# Sensor_Acquisition_Board_Rev3.net
KiCad netlist of a schematic drawn in EAGLE
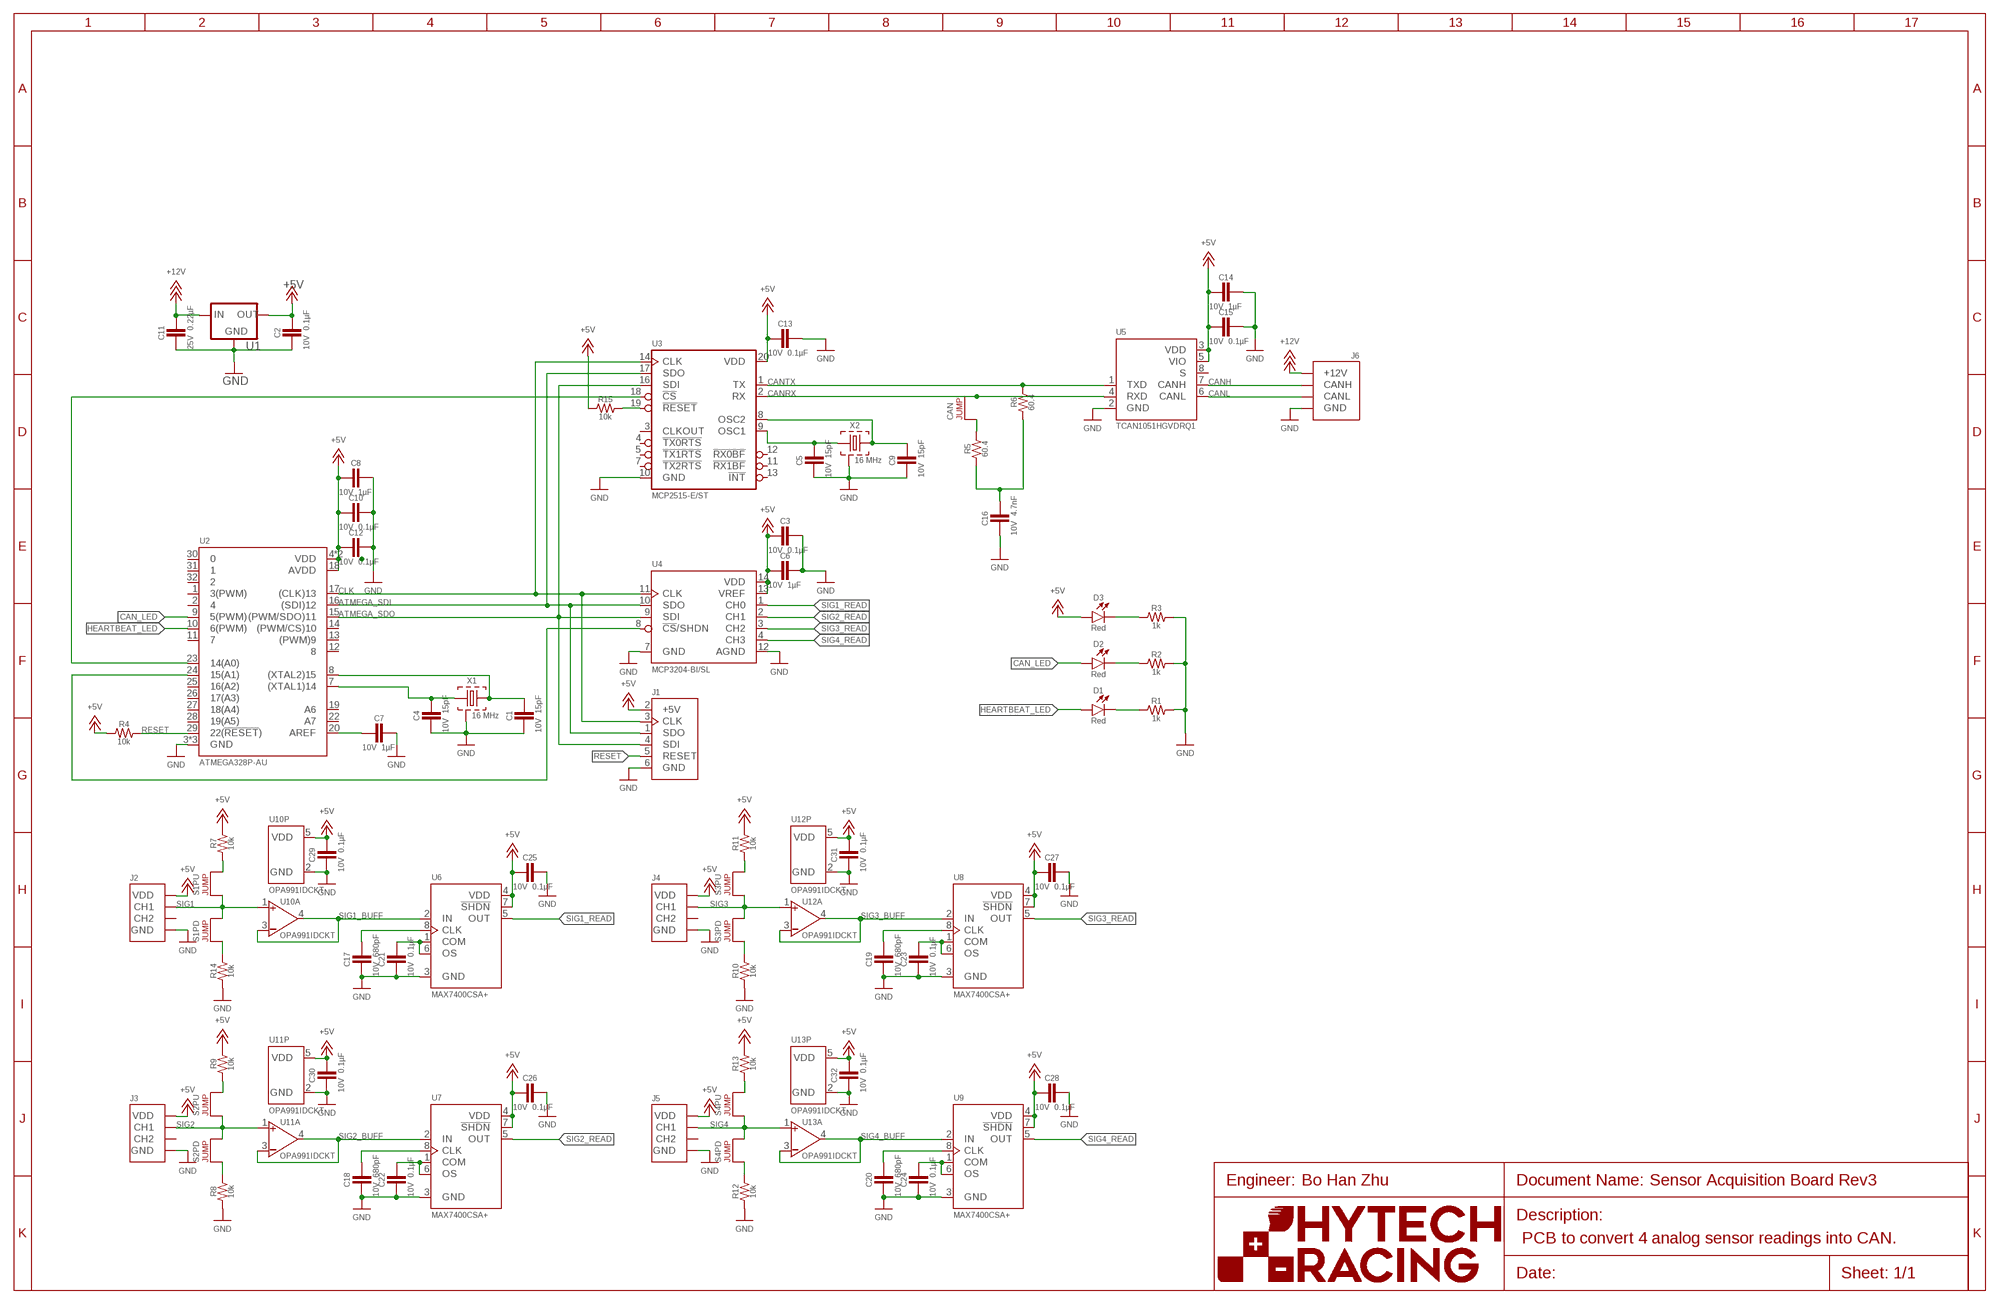
[diagram p0: schematic, sheet 1]

(export (version "E")
  (design (tool "Eeschema 10.0.6"))
  (components
    (comp (ref "C1")
      (value "CAPACITOR_0603_10V_15PF")
      (footprint "eagle-import:0603-CAP")
      (fields
        (field (name "CAPACITANCE") "15pF")
        (field (name "MANUFACTURER") "Vishay Vitramon")
        (field (name "MPN") "VJ0603A150FXQPW1BC")
        (field (name "TOLERANCE") "1%")
        (field (name "VOLTAGE") "10V")
      )
      (libsource (lib "eagle-import") (part "CAPACITOR_?_060310V_15PF"))
    )
    (comp (ref "C2")
      (value "CAPACITOR_0603_10V_0.1UF")
      (footprint "eagle-import:0603-CAP")
      (fields
        (field (name "CAPACITANCE") "0.1µF")
        (field (name "MANUFACTURER") "Vishay Vitramon")
        (field (name "MPN") "VJ0603Y104JXQPW1BC")
        (field (name "TOLERANCE") "5%")
        (field (name "VOLTAGE") "10V")
      )
      (libsource (lib "eagle-import") (part "CAPACITOR_?_060310V_0.1UF"))
    )
    (comp (ref "C3")
      (value "CAPACITOR_0603_10V_0.1UF")
      (footprint "eagle-import:0603-CAP")
      (fields
        (field (name "CAPACITANCE") "0.1µF")
        (field (name "MANUFACTURER") "Vishay Vitramon")
        (field (name "MPN") "VJ0603Y104JXQPW1BC")
        (field (name "TOLERANCE") "5%")
        (field (name "VOLTAGE") "10V")
      )
      (libsource (lib "eagle-import") (part "CAPACITOR_?_060310V_0.1UF"))
    )
    (comp (ref "C4")
      (value "CAPACITOR_0603_10V_15PF")
      (footprint "eagle-import:0603-CAP")
      (fields
        (field (name "CAPACITANCE") "15pF")
        (field (name "MANUFACTURER") "Vishay Vitramon")
        (field (name "MPN") "VJ0603A150FXQPW1BC")
        (field (name "TOLERANCE") "1%")
        (field (name "VOLTAGE") "10V")
      )
      (libsource (lib "eagle-import") (part "CAPACITOR_?_060310V_15PF"))
    )
    (comp (ref "C5")
      (value "CAPACITOR_0603_10V_15PF")
      (footprint "eagle-import:0603-CAP")
      (fields
        (field (name "CAPACITANCE") "15pF")
        (field (name "MANUFACTURER") "Vishay Vitramon")
        (field (name "MPN") "VJ0603A150FXQPW1BC")
        (field (name "TOLERANCE") "1%")
        (field (name "VOLTAGE") "10V")
      )
      (libsource (lib "eagle-import") (part "CAPACITOR_?_060310V_15PF"))
    )
    (comp (ref "C6")
      (value "CAPACITOR_0603_10V_1UF")
      (footprint "eagle-import:0603-CAP")
      (fields
        (field (name "CAPACITANCE") "1µF")
        (field (name "MANUFACTURER") "Yageo")
        (field (name "MPN") "CC0603KRX7R6BB105")
        (field (name "TOLERANCE") "10%")
        (field (name "VOLTAGE") "10V")
      )
      (libsource (lib "eagle-import") (part "CAPACITOR_?_060310V_1UF"))
    )
    (comp (ref "C7")
      (value "CAPACITOR_0603_10V_1UF")
      (footprint "eagle-import:0603-CAP")
      (fields
        (field (name "CAPACITANCE") "1µF")
        (field (name "MANUFACTURER") "Yageo")
        (field (name "MPN") "CC0603KRX7R6BB105")
        (field (name "TOLERANCE") "10%")
        (field (name "VOLTAGE") "10V")
      )
      (libsource (lib "eagle-import") (part "CAPACITOR_?_060310V_1UF"))
    )
    (comp (ref "C8")
      (value "CAPACITOR_0603_10V_1UF")
      (footprint "eagle-import:0603-CAP")
      (fields
        (field (name "CAPACITANCE") "1µF")
        (field (name "MANUFACTURER") "Yageo")
        (field (name "MPN") "CC0603KRX7R6BB105")
        (field (name "TOLERANCE") "10%")
        (field (name "VOLTAGE") "10V")
      )
      (libsource (lib "eagle-import") (part "CAPACITOR_?_060310V_1UF"))
    )
    (comp (ref "C9")
      (value "CAPACITOR_0603_10V_15PF")
      (footprint "eagle-import:0603-CAP")
      (fields
        (field (name "CAPACITANCE") "15pF")
        (field (name "MANUFACTURER") "Vishay Vitramon")
        (field (name "MPN") "VJ0603A150FXQPW1BC")
        (field (name "TOLERANCE") "1%")
        (field (name "VOLTAGE") "10V")
      )
      (libsource (lib "eagle-import") (part "CAPACITOR_?_060310V_15PF"))
    )
    (comp (ref "C10")
      (value "CAPACITOR_0603_10V_0.1UF")
      (footprint "eagle-import:0603-CAP")
      (fields
        (field (name "CAPACITANCE") "0.1µF")
        (field (name "MANUFACTURER") "Vishay Vitramon")
        (field (name "MPN") "VJ0603Y104JXQPW1BC")
        (field (name "TOLERANCE") "5%")
        (field (name "VOLTAGE") "10V")
      )
      (libsource (lib "eagle-import") (part "CAPACITOR_?_060310V_0.1UF"))
    )
    (comp (ref "C11")
      (value "CAPACITOR_0603_25V_0.22UF")
      (footprint "eagle-import:0603-CAP")
      (fields
        (field (name "CAPACITANCE") "0.22µF")
        (field (name "MANUFACTURER") "Walsin Technology Corporation")
        (field (name "MPN") "0603B224K250CT")
        (field (name "TOLERANCE") "10%")
        (field (name "VOLTAGE") "25V")
      )
      (libsource (lib "eagle-import") (part "CAPACITOR_?_060325V_0.22UF"))
    )
    (comp (ref "C12")
      (value "CAPACITOR_0603_10V_0.1UF")
      (footprint "eagle-import:0603-CAP")
      (fields
        (field (name "CAPACITANCE") "0.1µF")
        (field (name "MANUFACTURER") "Vishay Vitramon")
        (field (name "MPN") "VJ0603Y104JXQPW1BC")
        (field (name "TOLERANCE") "5%")
        (field (name "VOLTAGE") "10V")
      )
      (libsource (lib "eagle-import") (part "CAPACITOR_?_060310V_0.1UF"))
    )
    (comp (ref "C13")
      (value "CAPACITOR_0603_10V_0.1UF")
      (footprint "eagle-import:0603-CAP")
      (fields
        (field (name "CAPACITANCE") "0.1µF")
        (field (name "MANUFACTURER") "Vishay Vitramon")
        (field (name "MPN") "VJ0603Y104JXQPW1BC")
        (field (name "TOLERANCE") "5%")
        (field (name "VOLTAGE") "10V")
      )
      (libsource (lib "eagle-import") (part "CAPACITOR_?_060310V_0.1UF"))
    )
    (comp (ref "C14")
      (value "CAPACITOR_0603_10V_1UF")
      (footprint "eagle-import:0603-CAP")
      (fields
        (field (name "CAPACITANCE") "1µF")
        (field (name "MANUFACTURER") "Yageo")
        (field (name "MPN") "CC0603KRX7R6BB105")
        (field (name "TOLERANCE") "10%")
        (field (name "VOLTAGE") "10V")
      )
      (libsource (lib "eagle-import") (part "CAPACITOR_?_060310V_1UF"))
    )
    (comp (ref "C15")
      (value "CAPACITOR_0603_10V_0.1UF")
      (footprint "eagle-import:0603-CAP")
      (fields
        (field (name "CAPACITANCE") "0.1µF")
        (field (name "MANUFACTURER") "Vishay Vitramon")
        (field (name "MPN") "VJ0603Y104JXQPW1BC")
        (field (name "TOLERANCE") "5%")
        (field (name "VOLTAGE") "10V")
      )
      (libsource (lib "eagle-import") (part "CAPACITOR_?_060310V_0.1UF"))
    )
    (comp (ref "C16")
      (value "CAPACITOR_0603_10V_4.7NF")
      (footprint "eagle-import:0603-CAP")
      (fields
        (field (name "CAPACITANCE") "4.7nF")
        (field (name "MANUFACTURER") "Würth Elektronik")
        (field (name "MPN") "885012206012")
        (field (name "TOLERANCE") "10%")
        (field (name "VOLTAGE") "10V")
      )
      (libsource (lib "eagle-import") (part "CAPACITOR_?_060310V_4.7NF"))
    )
    (comp (ref "C17")
      (value "CAPACITOR_0603_10V_680PF")
      (footprint "eagle-import:0603-CAP")
      (fields
        (field (name "CAPACITANCE") "680pF")
        (field (name "MANUFACTURER") "Würth Elektronik")
        (field (name "MPN") "885012006013")
        (field (name "TOLERANCE") "5%")
        (field (name "VOLTAGE") "10V")
      )
      (libsource (lib "eagle-import") (part "CAPACITOR_?_060310V_680PF"))
    )
    (comp (ref "C18")
      (value "CAPACITOR_0603_10V_680PF")
      (footprint "eagle-import:0603-CAP")
      (fields
        (field (name "CAPACITANCE") "680pF")
        (field (name "MANUFACTURER") "Würth Elektronik")
        (field (name "MPN") "885012006013")
        (field (name "TOLERANCE") "5%")
        (field (name "VOLTAGE") "10V")
      )
      (libsource (lib "eagle-import") (part "CAPACITOR_?_060310V_680PF"))
    )
    (comp (ref "C19")
      (value "CAPACITOR_0603_10V_680PF")
      (footprint "eagle-import:0603-CAP")
      (fields
        (field (name "CAPACITANCE") "680pF")
        (field (name "MANUFACTURER") "Würth Elektronik")
        (field (name "MPN") "885012006013")
        (field (name "TOLERANCE") "5%")
        (field (name "VOLTAGE") "10V")
      )
      (libsource (lib "eagle-import") (part "CAPACITOR_?_060310V_680PF"))
    )
    (comp (ref "C20")
      (value "CAPACITOR_0603_10V_680PF")
      (footprint "eagle-import:0603-CAP")
      (fields
        (field (name "CAPACITANCE") "680pF")
        (field (name "MANUFACTURER") "Würth Elektronik")
        (field (name "MPN") "885012006013")
        (field (name "TOLERANCE") "5%")
        (field (name "VOLTAGE") "10V")
      )
      (libsource (lib "eagle-import") (part "CAPACITOR_?_060310V_680PF"))
    )
    (comp (ref "C21")
      (value "CAPACITOR_0603_10V_0.1UF")
      (footprint "eagle-import:0603-CAP")
      (fields
        (field (name "CAPACITANCE") "0.1µF")
        (field (name "MANUFACTURER") "Vishay Vitramon")
        (field (name "MPN") "VJ0603Y104JXQPW1BC")
        (field (name "TOLERANCE") "5%")
        (field (name "VOLTAGE") "10V")
      )
      (libsource (lib "eagle-import") (part "CAPACITOR_?_060310V_0.1UF"))
    )
    (comp (ref "C22")
      (value "CAPACITOR_0603_10V_0.1UF")
      (footprint "eagle-import:0603-CAP")
      (fields
        (field (name "CAPACITANCE") "0.1µF")
        (field (name "MANUFACTURER") "Vishay Vitramon")
        (field (name "MPN") "VJ0603Y104JXQPW1BC")
        (field (name "TOLERANCE") "5%")
        (field (name "VOLTAGE") "10V")
      )
      (libsource (lib "eagle-import") (part "CAPACITOR_?_060310V_0.1UF"))
    )
    (comp (ref "C23")
      (value "CAPACITOR_0603_10V_0.1UF")
      (footprint "eagle-import:0603-CAP")
      (fields
        (field (name "CAPACITANCE") "0.1µF")
        (field (name "MANUFACTURER") "Vishay Vitramon")
        (field (name "MPN") "VJ0603Y104JXQPW1BC")
        (field (name "TOLERANCE") "5%")
        (field (name "VOLTAGE") "10V")
      )
      (libsource (lib "eagle-import") (part "CAPACITOR_?_060310V_0.1UF"))
    )
    (comp (ref "C24")
      (value "CAPACITOR_0603_10V_0.1UF")
      (footprint "eagle-import:0603-CAP")
      (fields
        (field (name "CAPACITANCE") "0.1µF")
        (field (name "MANUFACTURER") "Vishay Vitramon")
        (field (name "MPN") "VJ0603Y104JXQPW1BC")
        (field (name "TOLERANCE") "5%")
        (field (name "VOLTAGE") "10V")
      )
      (libsource (lib "eagle-import") (part "CAPACITOR_?_060310V_0.1UF"))
    )
    (comp (ref "C25")
      (value "CAPACITOR_0603_10V_0.1UF")
      (footprint "eagle-import:0603-CAP")
      (fields
        (field (name "CAPACITANCE") "0.1µF")
        (field (name "MANUFACTURER") "Vishay Vitramon")
        (field (name "MPN") "VJ0603Y104JXQPW1BC")
        (field (name "TOLERANCE") "5%")
        (field (name "VOLTAGE") "10V")
      )
      (libsource (lib "eagle-import") (part "CAPACITOR_?_060310V_0.1UF"))
    )
    (comp (ref "C26")
      (value "CAPACITOR_0603_10V_0.1UF")
      (footprint "eagle-import:0603-CAP")
      (fields
        (field (name "CAPACITANCE") "0.1µF")
        (field (name "MANUFACTURER") "Vishay Vitramon")
        (field (name "MPN") "VJ0603Y104JXQPW1BC")
        (field (name "TOLERANCE") "5%")
        (field (name "VOLTAGE") "10V")
      )
      (libsource (lib "eagle-import") (part "CAPACITOR_?_060310V_0.1UF"))
    )
    (comp (ref "C27")
      (value "CAPACITOR_0603_10V_0.1UF")
      (footprint "eagle-import:0603-CAP")
      (fields
        (field (name "CAPACITANCE") "0.1µF")
        (field (name "MANUFACTURER") "Vishay Vitramon")
        (field (name "MPN") "VJ0603Y104JXQPW1BC")
        (field (name "TOLERANCE") "5%")
        (field (name "VOLTAGE") "10V")
      )
      (libsource (lib "eagle-import") (part "CAPACITOR_?_060310V_0.1UF"))
    )
    (comp (ref "C28")
      (value "CAPACITOR_0603_10V_0.1UF")
      (footprint "eagle-import:0603-CAP")
      (fields
        (field (name "CAPACITANCE") "0.1µF")
        (field (name "MANUFACTURER") "Vishay Vitramon")
        (field (name "MPN") "VJ0603Y104JXQPW1BC")
        (field (name "TOLERANCE") "5%")
        (field (name "VOLTAGE") "10V")
      )
      (libsource (lib "eagle-import") (part "CAPACITOR_?_060310V_0.1UF"))
    )
    (comp (ref "C29")
      (value "CAPACITOR_0603_10V_0.1UF")
      (footprint "eagle-import:0603-CAP")
      (fields
        (field (name "CAPACITANCE") "0.1µF")
        (field (name "MANUFACTURER") "Vishay Vitramon")
        (field (name "MPN") "VJ0603Y104JXQPW1BC")
        (field (name "TOLERANCE") "5%")
        (field (name "VOLTAGE") "10V")
      )
      (libsource (lib "eagle-import") (part "CAPACITOR_?_060310V_0.1UF"))
    )
    (comp (ref "C30")
      (value "CAPACITOR_0603_10V_0.1UF")
      (footprint "eagle-import:0603-CAP")
      (fields
        (field (name "CAPACITANCE") "0.1µF")
        (field (name "MANUFACTURER") "Vishay Vitramon")
        (field (name "MPN") "VJ0603Y104JXQPW1BC")
        (field (name "TOLERANCE") "5%")
        (field (name "VOLTAGE") "10V")
      )
      (libsource (lib "eagle-import") (part "CAPACITOR_?_060310V_0.1UF"))
    )
    (comp (ref "C31")
      (value "CAPACITOR_0603_10V_0.1UF")
      (footprint "eagle-import:0603-CAP")
      (fields
        (field (name "CAPACITANCE") "0.1µF")
        (field (name "MANUFACTURER") "Vishay Vitramon")
        (field (name "MPN") "VJ0603Y104JXQPW1BC")
        (field (name "TOLERANCE") "5%")
        (field (name "VOLTAGE") "10V")
      )
      (libsource (lib "eagle-import") (part "CAPACITOR_?_060310V_0.1UF"))
    )
    (comp (ref "C32")
      (value "CAPACITOR_0603_10V_0.1UF")
      (footprint "eagle-import:0603-CAP")
      (fields
        (field (name "CAPACITANCE") "0.1µF")
        (field (name "MANUFACTURER") "Vishay Vitramon")
        (field (name "MPN") "VJ0603Y104JXQPW1BC")
        (field (name "TOLERANCE") "5%")
        (field (name "VOLTAGE") "10V")
      )
      (libsource (lib "eagle-import") (part "CAPACITOR_?_060310V_0.1UF"))
    )
    (comp (ref "CAN")
      (value "JUMPER_1X02_")
      (footprint "eagle-import:1X02")
      (libsource (lib "eagle-import") (part "JUMPER_?_1X02"))
    )
    (comp (ref "D1")
      (value "LED_0603_RED")
      (footprint "eagle-import:0603-LED")
      (fields
        (field (name "COLOR") "Red")
        (field (name "MANUFACTURER") "Kingbright")
        (field (name "MPN") "APT1608SECK/J3-PRV")
      )
      (libsource (lib "eagle-import") (part "LED_?_0603RED"))
    )
    (comp (ref "D2")
      (value "LED_0603_RED")
      (footprint "eagle-import:0603-LED")
      (fields
        (field (name "COLOR") "Red")
        (field (name "MANUFACTURER") "Kingbright")
        (field (name "MPN") "APT1608SECK/J3-PRV")
      )
      (libsource (lib "eagle-import") (part "LED_?_0603RED"))
    )
    (comp (ref "D3")
      (value "LED_0603_RED")
      (footprint "eagle-import:0603-LED")
      (fields
        (field (name "COLOR") "Red")
        (field (name "MANUFACTURER") "Kingbright")
        (field (name "MPN") "APT1608SECK/J3-PRV")
      )
      (libsource (lib "eagle-import") (part "LED_?_0603RED"))
    )
    (comp (ref "J1")
      (value "CONNECTOR-AVR-ISP__")
      (footprint "eagle-import:2X03")
      (libsource (lib "eagle-import") (part "CONNECTOR-AVR-ISP_?_"))
    )
    (comp (ref "J2")
      (value "CONNECTOR-SENSOR_NF_S_RA_BLACK")
      (footprint "eagle-import:MOLEX_NANOFIT_SMD_RIGHTANGLE_04")
      (fields (field (name "MANUFACTURER") "Molex") (field (name "MPN") "105405-1304"))
      (libsource (lib "eagle-import") (part "CONNECTOR-SENSOR_?_NF_S_RABLACK"))
    )
    (comp (ref "J3")
      (value "CONNECTOR-SENSOR_NF_S_RA_BLACK")
      (footprint "eagle-import:MOLEX_NANOFIT_SMD_RIGHTANGLE_04")
      (fields (field (name "MANUFACTURER") "Molex") (field (name "MPN") "105405-1304"))
      (libsource (lib "eagle-import") (part "CONNECTOR-SENSOR_?_NF_S_RABLACK"))
    )
    (comp (ref "J4")
      (value "CONNECTOR-SENSOR_NF_S_RA_BLACK")
      (footprint "eagle-import:MOLEX_NANOFIT_SMD_RIGHTANGLE_04")
      (fields (field (name "MANUFACTURER") "Molex") (field (name "MPN") "105405-1304"))
      (libsource (lib "eagle-import") (part "CONNECTOR-SENSOR_?_NF_S_RABLACK"))
    )
    (comp (ref "J5")
      (value "CONNECTOR-SENSOR_NF_S_RA_BLACK")
      (footprint "eagle-import:MOLEX_NANOFIT_SMD_RIGHTANGLE_04")
      (fields (field (name "MANUFACTURER") "Molex") (field (name "MPN") "105405-1304"))
      (libsource (lib "eagle-import") (part "CONNECTOR-SENSOR_?_NF_S_RABLACK"))
    )
    (comp (ref "J6")
      (value "CONNECTOR-CAN_NF_S_RA_BLACK")
      (footprint "eagle-import:MOLEX_NANOFIT_SMD_RIGHTANGLE_04")
      (fields (field (name "MANUFACTURER") "Molex") (field (name "MPN") "105405-1304"))
      (libsource (lib "eagle-import") (part "CONNECTOR-CAN_?_NF_S_RABLACK"))
    )
    (comp (ref "R1")
      (value "RESISTOR_0603_1K")
      (footprint "eagle-import:0603-RES")
      (fields
        (field (name "MANUFACTURER") "Yageo")
        (field (name "MPN") "RC0603FR-071KL")
        (field (name "POWER") "0.1W")
        (field (name "RESISTANCE") "1k")
      )
      (libsource (lib "eagle-import") (part "RESISTOR_?_06031K"))
    )
    (comp (ref "R2")
      (value "RESISTOR_0603_1K")
      (footprint "eagle-import:0603-RES")
      (fields
        (field (name "MANUFACTURER") "Yageo")
        (field (name "MPN") "RC0603FR-071KL")
        (field (name "POWER") "0.1W")
        (field (name "RESISTANCE") "1k")
      )
      (libsource (lib "eagle-import") (part "RESISTOR_?_06031K"))
    )
    (comp (ref "R3")
      (value "RESISTOR_0603_1K")
      (footprint "eagle-import:0603-RES")
      (fields
        (field (name "MANUFACTURER") "Yageo")
        (field (name "MPN") "RC0603FR-071KL")
        (field (name "POWER") "0.1W")
        (field (name "RESISTANCE") "1k")
      )
      (libsource (lib "eagle-import") (part "RESISTOR_?_06031K"))
    )
    (comp (ref "R4")
      (value "RESISTOR_0603_10K")
      (footprint "eagle-import:0603-RES")
      (fields
        (field (name "MANUFACTURER") "Yageo")
        (field (name "MPN") "RC0603FR-0710KL")
        (field (name "POWER") "0.1W")
        (field (name "RESISTANCE") "10k")
      )
      (libsource (lib "eagle-import") (part "RESISTOR_?_060310K"))
    )
    (comp (ref "R5")
      (value "RESISTOR_0603_60.4")
      (footprint "eagle-import:0603-RES")
      (fields
        (field (name "MANUFACTURER") "Yageo")
        (field (name "MPN") "RC0603FR-0760R4L")
        (field (name "POWER") "0.1W")
        (field (name "RESISTANCE") "60.4")
      )
      (libsource (lib "eagle-import") (part "RESISTOR_?_060360.4"))
    )
    (comp (ref "R6")
      (value "RESISTOR_0603_60.4")
      (footprint "eagle-import:0603-RES")
      (fields
        (field (name "MANUFACTURER") "Yageo")
        (field (name "MPN") "RC0603FR-0760R4L")
        (field (name "POWER") "0.1W")
        (field (name "RESISTANCE") "60.4")
      )
      (libsource (lib "eagle-import") (part "RESISTOR_?_060360.4"))
    )
    (comp (ref "R7")
      (value "RESISTOR_0603_10K")
      (footprint "eagle-import:0603-RES")
      (fields
        (field (name "MANUFACTURER") "Yageo")
        (field (name "MPN") "RC0603FR-0710KL")
        (field (name "POWER") "0.1W")
        (field (name "RESISTANCE") "10k")
      )
      (libsource (lib "eagle-import") (part "RESISTOR_?_060310K"))
    )
    (comp (ref "R8")
      (value "RESISTOR_0603_10K")
      (footprint "eagle-import:0603-RES")
      (fields
        (field (name "MANUFACTURER") "Yageo")
        (field (name "MPN") "RC0603FR-0710KL")
        (field (name "POWER") "0.1W")
        (field (name "RESISTANCE") "10k")
      )
      (libsource (lib "eagle-import") (part "RESISTOR_?_060310K"))
    )
    (comp (ref "R9")
      (value "RESISTOR_0603_10K")
      (footprint "eagle-import:0603-RES")
      (fields
        (field (name "MANUFACTURER") "Yageo")
        (field (name "MPN") "RC0603FR-0710KL")
        (field (name "POWER") "0.1W")
        (field (name "RESISTANCE") "10k")
      )
      (libsource (lib "eagle-import") (part "RESISTOR_?_060310K"))
    )
    (comp (ref "R10")
      (value "RESISTOR_0603_10K")
      (footprint "eagle-import:0603-RES")
      (fields
        (field (name "MANUFACTURER") "Yageo")
        (field (name "MPN") "RC0603FR-0710KL")
        (field (name "POWER") "0.1W")
        (field (name "RESISTANCE") "10k")
      )
      (libsource (lib "eagle-import") (part "RESISTOR_?_060310K"))
    )
    (comp (ref "R11")
      (value "RESISTOR_0603_10K")
      (footprint "eagle-import:0603-RES")
      (fields
        (field (name "MANUFACTURER") "Yageo")
        (field (name "MPN") "RC0603FR-0710KL")
        (field (name "POWER") "0.1W")
        (field (name "RESISTANCE") "10k")
      )
      (libsource (lib "eagle-import") (part "RESISTOR_?_060310K"))
    )
    (comp (ref "R12")
      (value "RESISTOR_0603_10K")
      (footprint "eagle-import:0603-RES")
      (fields
        (field (name "MANUFACTURER") "Yageo")
        (field (name "MPN") "RC0603FR-0710KL")
        (field (name "POWER") "0.1W")
        (field (name "RESISTANCE") "10k")
      )
      (libsource (lib "eagle-import") (part "RESISTOR_?_060310K"))
    )
    (comp (ref "R13")
      (value "RESISTOR_0603_10K")
      (footprint "eagle-import:0603-RES")
      (fields
        (field (name "MANUFACTURER") "Yageo")
        (field (name "MPN") "RC0603FR-0710KL")
        (field (name "POWER") "0.1W")
        (field (name "RESISTANCE") "10k")
      )
      (libsource (lib "eagle-import") (part "RESISTOR_?_060310K"))
    )
    (comp (ref "R14")
      (value "RESISTOR_0603_10K")
      (footprint "eagle-import:0603-RES")
      (fields
        (field (name "MANUFACTURER") "Yageo")
        (field (name "MPN") "RC0603FR-0710KL")
        (field (name "POWER") "0.1W")
        (field (name "RESISTANCE") "10k")
      )
      (libsource (lib "eagle-import") (part "RESISTOR_?_060310K"))
    )
    (comp (ref "R15")
      (value "RESISTOR_0603_10K")
      (footprint "eagle-import:0603-RES")
      (fields
        (field (name "MANUFACTURER") "Yageo")
        (field (name "MPN") "RC0603FR-0710KL")
        (field (name "POWER") "0.1W")
        (field (name "RESISTANCE") "10k")
      )
      (libsource (lib "eagle-import") (part "RESISTOR_?_060310K"))
    )
    (comp (ref "S1PD")
      (value "JUMPER_1X02_")
      (footprint "eagle-import:1X02")
      (libsource (lib "eagle-import") (part "JUMPER_?_1X02"))
    )
    (comp (ref "S1PU")
      (value "JUMPER_1X02_")
      (footprint "eagle-import:1X02")
      (libsource (lib "eagle-import") (part "JUMPER_?_1X02"))
    )
    (comp (ref "S2PD")
      (value "JUMPER_1X02_")
      (footprint "eagle-import:1X02")
      (libsource (lib "eagle-import") (part "JUMPER_?_1X02"))
    )
    (comp (ref "S2PU")
      (value "JUMPER_1X02_")
      (footprint "eagle-import:1X02")
      (libsource (lib "eagle-import") (part "JUMPER_?_1X02"))
    )
    (comp (ref "S3PD")
      (value "JUMPER_1X02_")
      (footprint "eagle-import:1X02")
      (libsource (lib "eagle-import") (part "JUMPER_?_1X02"))
    )
    (comp (ref "S3PU")
      (value "JUMPER_1X02_")
      (footprint "eagle-import:1X02")
      (libsource (lib "eagle-import") (part "JUMPER_?_1X02"))
    )
    (comp (ref "S4PD")
      (value "JUMPER_1X02_")
      (footprint "eagle-import:1X02")
      (libsource (lib "eagle-import") (part "JUMPER_?_1X02"))
    )
    (comp (ref "S4PU")
      (value "JUMPER_1X02_")
      (footprint "eagle-import:1X02")
      (libsource (lib "eagle-import") (part "JUMPER_?_1X02"))
    )
    (comp (ref "U1")
      (value "LM340")
      (footprint "eagle-import:SOT223")
      (libsource (lib "eagle-import") (part "LM340"))
    )
    (comp (ref "U2")
      (value "ATMEGA328P-AU")
      (footprint "eagle-import:TQFP-32")
      (fields (field (name "MPN") "ATMEGA328P-AU") (field (name "MANUFACTURER") "Microchip Technology"))
      (libsource (lib "eagle-import") (part "ATMEGA328P-AU"))
    )
    (comp (ref "U3")
      (value "MCP2515")
      (footprint "eagle-import:TSSOP-20")
      (fields (field (name "MPN") "MCP2515-E/ST") (field (name "MANUFACTURER") "Microchip Technology"))
      (libsource (lib "eagle-import") (part "MCP2515"))
    )
    (comp (ref "U4")
      (value "MCP3204")
      (footprint "eagle-import:SOIC-14")
      (fields (field (name "MPN") "MCP3204-BI/SL") (field (name "MANUFACTURER") "Microchip Technology"))
      (libsource (lib "eagle-import") (part "MCP3204"))
    )
    (comp (ref "U5")
      (value "CAN_TRANSCIEVER_TCAN1051HQV-Q1")
      (footprint "eagle-import:SOIC-08")
      (fields (field (name "MANUFACTURER") "Texas Instruments") (field (name "MPN") "TCAN1051HGVDRQ1"))
      (libsource (lib "eagle-import") (part "CAN_TRANSCIEVER_TCAN1051V-Q1HQ"))
    )
    (comp (ref "U6")
      (value "MAX7400")
      (footprint "eagle-import:SOIC-08(NARROW,0.15_)")
      (fields (field (name "MANUFACTURER") "Maxim Integrated") (field (name "MPN") "MAX7400CSA+"))
      (libsource (lib "eagle-import") (part "MAX7400"))
    )
    (comp (ref "U7")
      (value "MAX7400")
      (footprint "eagle-import:SOIC-08(NARROW,0.15_)")
      (fields (field (name "MANUFACTURER") "Maxim Integrated") (field (name "MPN") "MAX7400CSA+"))
      (libsource (lib "eagle-import") (part "MAX7400"))
    )
    (comp (ref "U8")
      (value "MAX7400")
      (footprint "eagle-import:SOIC-08(NARROW,0.15_)")
      (fields (field (name "MANUFACTURER") "Maxim Integrated") (field (name "MPN") "MAX7400CSA+"))
      (libsource (lib "eagle-import") (part "MAX7400"))
    )
    (comp (ref "U9")
      (value "MAX7400")
      (footprint "eagle-import:SOIC-08(NARROW,0.15_)")
      (fields (field (name "MANUFACTURER") "Maxim Integrated") (field (name "MPN") "MAX7400CSA+"))
      (libsource (lib "eagle-import") (part "MAX7400"))
    )
    (comp (ref "U10")
      (value "OPAMP_1_CHANNEL_OPA991")
      (footprint "eagle-import:SC-70-5")
      (fields (field (name "MPN") "OPA991IDCKT"))
      (libsource (lib "eagle-import") (part "OPAMP_1_CHANNEL_OPA991"))
    )
    (comp (ref "U11")
      (value "OPAMP_1_CHANNEL_OPA991")
      (footprint "eagle-import:SC-70-5")
      (fields (field (name "MPN") "OPA991IDCKT"))
      (libsource (lib "eagle-import") (part "OPAMP_1_CHANNEL_OPA991"))
    )
    (comp (ref "U12")
      (value "OPAMP_1_CHANNEL_OPA991")
      (footprint "eagle-import:SC-70-5")
      (fields (field (name "MPN") "OPA991IDCKT"))
      (libsource (lib "eagle-import") (part "OPAMP_1_CHANNEL_OPA991"))
    )
    (comp (ref "U13")
      (value "OPAMP_1_CHANNEL_OPA991")
      (footprint "eagle-import:SC-70-5")
      (fields (field (name "MPN") "OPA991IDCKT"))
      (libsource (lib "eagle-import") (part "OPAMP_1_CHANNEL_OPA991"))
    )
    (comp (ref "X1")
      (value "CRYSTAL16MHZ")
      (footprint "eagle-import:ABM3B")
      (fields
        (field (name "FREQUENCY") "16 MHz")
        (field (name "MANUFACTURER") "TXC CORPORATION")
        (field (name "MPN") "7B-16.000MEEQ-T")
      )
      (libsource (lib "eagle-import") (part "CRYSTAL16MHZ"))
    )
    (comp (ref "X2")
      (value "CRYSTAL16MHZ")
      (footprint "eagle-import:ABM3B")
      (fields
        (field (name "FREQUENCY") "16 MHz")
        (field (name "MANUFACTURER") "TXC CORPORATION")
        (field (name "MPN") "7B-16.000MEEQ-T")
      )
      (libsource (lib "eagle-import") (part "CRYSTAL16MHZ"))
    )
  )
  (nets
    (net (code "1") (name "+5V") (class "Default")
      (node (ref "C10") (pin "2") (pinfunction "2_2") (pintype "passive"))
      (node (ref "C12") (pin "2") (pinfunction "2_2") (pintype "passive"))
      (node (ref "C13") (pin "2") (pinfunction "2_2") (pintype "passive"))
      (node (ref "C14") (pin "2") (pinfunction "2_2") (pintype "passive"))
      (node (ref "C15") (pin "2") (pinfunction "2_2") (pintype "passive"))
      (node (ref "C2") (pin "1") (pinfunction "1_1") (pintype "passive"))
      (node (ref "C25") (pin "2") (pinfunction "2_2") (pintype "passive"))
      (node (ref "C26") (pin "2") (pinfunction "2_2") (pintype "passive"))
      (node (ref "C27") (pin "2") (pinfunction "2_2") (pintype "passive"))
      (node (ref "C28") (pin "2") (pinfunction "2_2") (pintype "passive"))
      (node (ref "C29") (pin "1") (pinfunction "1_1") (pintype "passive"))
      (node (ref "C3") (pin "2") (pinfunction "2_2") (pintype "passive"))
      (node (ref "C30") (pin "1") (pinfunction "1_1") (pintype "passive"))
      (node (ref "C31") (pin "1") (pinfunction "1_1") (pintype "passive"))
      (node (ref "C32") (pin "1") (pinfunction "1_1") (pintype "passive"))
      (node (ref "C6") (pin "2") (pinfunction "2_2") (pintype "passive"))
      (node (ref "C8") (pin "2") (pinfunction "2_2") (pintype "passive"))
      (node (ref "D3") (pin "2") (pinfunction "A_2") (pintype "passive"))
      (node (ref "J1") (pin "2") (pinfunction "+5V_2") (pintype "power_in"))
      (node (ref "J2") (pin "1") (pinfunction "VDD_1") (pintype "power_in"))
      (node (ref "J3") (pin "1") (pinfunction "VDD_1") (pintype "power_in"))
      (node (ref "J4") (pin "1") (pinfunction "VDD_1") (pintype "power_in"))
      (node (ref "J5") (pin "1") (pinfunction "VDD_1") (pintype "power_in"))
      (node (ref "R11") (pin "2") (pinfunction "2_2") (pintype "passive"))
      (node (ref "R13") (pin "2") (pinfunction "2_2") (pintype "passive"))
      (node (ref "R15") (pin "1") (pinfunction "1_1") (pintype "passive"))
      (node (ref "R4") (pin "1") (pinfunction "1_1") (pintype "passive"))
      (node (ref "R7") (pin "2") (pinfunction "2_2") (pintype "passive"))
      (node (ref "R9") (pin "2") (pinfunction "2_2") (pintype "passive"))
      (node (ref "U1") (pin "3") (pinfunction "OUT_3") (pintype "output"))
      (node (ref "U10") (pin "5") (pinfunction "VDD_5") (pintype "power_in"))
      (node (ref "U11") (pin "5") (pinfunction "VDD_5") (pintype "power_in"))
      (node (ref "U12") (pin "5") (pinfunction "VDD_5") (pintype "power_in"))
      (node (ref "U13") (pin "5") (pinfunction "VDD_5") (pintype "power_in"))
      (node (ref "U2") (pin "18") (pinfunction "AVDD_18") (pintype "power_in"))
      (node (ref "U2") (pin "4") (pinfunction "VDD_4") (pintype "power_in"))
      (node (ref "U2") (pin "6") (pinfunction "VDD_6") (pintype "power_in"))
      (node (ref "U3") (pin "20") (pinfunction "VDD_20") (pintype "power_in"))
      (node (ref "U4") (pin "13") (pinfunction "VREF_13") (pintype "power_in"))
      (node (ref "U4") (pin "14") (pinfunction "VDD_14") (pintype "power_in"))
      (node (ref "U5") (pin "3") (pinfunction "VDD_3") (pintype "power_in"))
      (node (ref "U5") (pin "5") (pinfunction "VIO_5") (pintype "power_in"))
      (node (ref "U6") (pin "4") (pinfunction "VDD_4") (pintype "power_in"))
      (node (ref "U6") (pin "7") (pinfunction "~{SHDN}_7") (pintype "input"))
      (node (ref "U7") (pin "4") (pinfunction "VDD_4") (pintype "power_in"))
      (node (ref "U7") (pin "7") (pinfunction "~{SHDN}_7") (pintype "input"))
      (node (ref "U8") (pin "4") (pinfunction "VDD_4") (pintype "power_in"))
      (node (ref "U8") (pin "7") (pinfunction "~{SHDN}_7") (pintype "input"))
      (node (ref "U9") (pin "4") (pinfunction "VDD_4") (pintype "power_in"))
      (node (ref "U9") (pin "7") (pinfunction "~{SHDN}_7") (pintype "input"))
    )
    (net (code "2") (name "+12V") (class "Default")
      (node (ref "C11") (pin "1") (pinfunction "1_1") (pintype "passive"))
      (node (ref "J6") (pin "1") (pinfunction "+12V_1") (pintype "power_in"))
      (node (ref "U1") (pin "1") (pinfunction "IN_1") (pintype "input"))
    )
    (net (code "3") (name "/ATMEGA_SDI") (class "Default")
      (node (ref "J1") (pin "1") (pinfunction "SDO_1") (pintype "output"))
      (node (ref "U2") (pin "16") (pinfunction "(SDI)12_16") (pintype "bidirectional"))
      (node (ref "U3") (pin "17") (pinfunction "SDO_17") (pintype "output"))
      (node (ref "U4") (pin "10") (pinfunction "SDO_10") (pintype "output"))
    )
    (net (code "4") (name "/ATMEGA_SDO") (class "Default")
      (node (ref "J1") (pin "4") (pinfunction "SDI_4") (pintype "input"))
      (node (ref "U2") (pin "15") (pinfunction "(PWM/SDO)11_15") (pintype "bidirectional"))
      (node (ref "U3") (pin "16") (pinfunction "SDI_16") (pintype "input"))
      (node (ref "U4") (pin "9") (pinfunction "SDI_9") (pintype "input"))
    )
    (net (code "5") (name "/CANH") (class "Default")
      (node (ref "J6") (pin "4") (pinfunction "CANH_4") (pintype "bidirectional"))
      (node (ref "U5") (pin "7") (pinfunction "CANH_7") (pintype "output"))
    )
    (net (code "6") (name "/CANL") (class "Default")
      (node (ref "J6") (pin "3") (pinfunction "CANL_3") (pintype "bidirectional"))
      (node (ref "U5") (pin "6") (pinfunction "CANL_6") (pintype "bidirectional"))
    )
    (net (code "7") (name "/CANRX") (class "Default")
      (node (ref "CAN") (pin "2") (pinfunction "P$2_2") (pintype "passive"))
      (node (ref "U3") (pin "2") (pinfunction "RX_2") (pintype "input"))
      (node (ref "U5") (pin "4") (pinfunction "RXD_4") (pintype "output"))
    )
    (net (code "8") (name "/CANTX") (class "Default")
      (node (ref "R6") (pin "2") (pinfunction "2_2") (pintype "passive"))
      (node (ref "U3") (pin "1") (pinfunction "TX_1") (pintype "output"))
      (node (ref "U5") (pin "1") (pinfunction "TXD_1") (pintype "input"))
    )
    (net (code "9") (name "/CLK") (class "Default")
      (node (ref "J1") (pin "3") (pinfunction "CLK_3") (pintype "bidirectional"))
      (node (ref "U2") (pin "17") (pinfunction "(CLK)13_17") (pintype "bidirectional"))
      (node (ref "U3") (pin "14") (pinfunction "CLK_14") (pintype "input"))
      (node (ref "U4") (pin "11") (pinfunction "CLK_11") (pintype "input"))
    )
    (net (code "10") (name "/SIG1") (class "Default")
      (node (ref "J2") (pin "3") (pinfunction "CH1_3") (pintype "output"))
      (node (ref "S1PD") (pin "2") (pinfunction "P$2_2") (pintype "passive"))
      (node (ref "S1PU") (pin "1") (pinfunction "P$1_1") (pintype "passive"))
      (node (ref "U10") (pin "1") (pinfunction "VIN+_1") (pintype "input"))
    )
    (net (code "11") (name "/SIG1_BUFF") (class "Default")
      (node (ref "U10") (pin "3") (pinfunction "VIN-_3") (pintype "input"))
      (node (ref "U10") (pin "4") (pinfunction "VOUT_4") (pintype "output"))
      (node (ref "U6") (pin "2") (pinfunction "IN_2") (pintype "input"))
    )
    (net (code "12") (name "/SIG2") (class "Default")
      (node (ref "J3") (pin "3") (pinfunction "CH1_3") (pintype "output"))
      (node (ref "S2PD") (pin "2") (pinfunction "P$2_2") (pintype "passive"))
      (node (ref "S2PU") (pin "1") (pinfunction "P$1_1") (pintype "passive"))
      (node (ref "U11") (pin "1") (pinfunction "VIN+_1") (pintype "input"))
    )
    (net (code "13") (name "/SIG2_BUFF") (class "Default")
      (node (ref "U11") (pin "3") (pinfunction "VIN-_3") (pintype "input"))
      (node (ref "U11") (pin "4") (pinfunction "VOUT_4") (pintype "output"))
      (node (ref "U7") (pin "2") (pinfunction "IN_2") (pintype "input"))
    )
    (net (code "14") (name "/SIG3") (class "Default")
      (node (ref "J4") (pin "3") (pinfunction "CH1_3") (pintype "output"))
      (node (ref "S3PD") (pin "2") (pinfunction "P$2_2") (pintype "passive"))
      (node (ref "S3PU") (pin "1") (pinfunction "P$1_1") (pintype "passive"))
      (node (ref "U12") (pin "1") (pinfunction "VIN+_1") (pintype "input"))
    )
    (net (code "15") (name "/SIG3_BUFF") (class "Default")
      (node (ref "U12") (pin "3") (pinfunction "VIN-_3") (pintype "input"))
      (node (ref "U12") (pin "4") (pinfunction "VOUT_4") (pintype "output"))
      (node (ref "U8") (pin "2") (pinfunction "IN_2") (pintype "input"))
    )
    (net (code "16") (name "/SIG4") (class "Default")
      (node (ref "J5") (pin "3") (pinfunction "CH1_3") (pintype "output"))
      (node (ref "S4PD") (pin "2") (pinfunction "P$2_2") (pintype "passive"))
      (node (ref "S4PU") (pin "1") (pinfunction "P$1_1") (pintype "passive"))
      (node (ref "U13") (pin "1") (pinfunction "VIN+_1") (pintype "input"))
    )
    (net (code "17") (name "/SIG4_BUFF") (class "Default")
      (node (ref "U13") (pin "3") (pinfunction "VIN-_3") (pintype "input"))
      (node (ref "U13") (pin "4") (pinfunction "VOUT_4") (pintype "output"))
      (node (ref "U9") (pin "2") (pinfunction "IN_2") (pintype "input"))
    )
    (net (code "18") (name "CAN_LED") (class "Default")
      (node (ref "D2") (pin "2") (pinfunction "A_2") (pintype "passive"))
      (node (ref "U2") (pin "9") (pinfunction "5(PWM)_9") (pintype "bidirectional"))
    )
    (net (code "19") (name "GND") (class "Default")
      (node (ref "C1") (pin "2") (pinfunction "2_2") (pintype "passive"))
      (node (ref "C10") (pin "1") (pinfunction "1_1") (pintype "passive"))
      (node (ref "C11") (pin "2") (pinfunction "2_2") (pintype "passive"))
      (node (ref "C12") (pin "1") (pinfunction "1_1") (pintype "passive"))
      (node (ref "C13") (pin "1") (pinfunction "1_1") (pintype "passive"))
      (node (ref "C14") (pin "1") (pinfunction "1_1") (pintype "passive"))
      (node (ref "C15") (pin "1") (pinfunction "1_1") (pintype "passive"))
      (node (ref "C16") (pin "2") (pinfunction "2_2") (pintype "passive"))
      (node (ref "C17") (pin "2") (pinfunction "2_2") (pintype "passive"))
      (node (ref "C18") (pin "2") (pinfunction "2_2") (pintype "passive"))
      (node (ref "C19") (pin "2") (pinfunction "2_2") (pintype "passive"))
      (node (ref "C2") (pin "2") (pinfunction "2_2") (pintype "passive"))
      (node (ref "C20") (pin "2") (pinfunction "2_2") (pintype "passive"))
      (node (ref "C21") (pin "2") (pinfunction "2_2") (pintype "passive"))
      (node (ref "C22") (pin "2") (pinfunction "2_2") (pintype "passive"))
      (node (ref "C23") (pin "2") (pinfunction "2_2") (pintype "passive"))
      (node (ref "C24") (pin "2") (pinfunction "2_2") (pintype "passive"))
      (node (ref "C25") (pin "1") (pinfunction "1_1") (pintype "passive"))
      (node (ref "C26") (pin "1") (pinfunction "1_1") (pintype "passive"))
      (node (ref "C27") (pin "1") (pinfunction "1_1") (pintype "passive"))
      (node (ref "C28") (pin "1") (pinfunction "1_1") (pintype "passive"))
      (node (ref "C29") (pin "2") (pinfunction "2_2") (pintype "passive"))
      (node (ref "C3") (pin "1") (pinfunction "1_1") (pintype "passive"))
      (node (ref "C30") (pin "2") (pinfunction "2_2") (pintype "passive"))
      (node (ref "C31") (pin "2") (pinfunction "2_2") (pintype "passive"))
      (node (ref "C32") (pin "2") (pinfunction "2_2") (pintype "passive"))
      (node (ref "C4") (pin "2") (pinfunction "2_2") (pintype "passive"))
      (node (ref "C5") (pin "2") (pinfunction "2_2") (pintype "passive"))
      (node (ref "C6") (pin "1") (pinfunction "1_1") (pintype "passive"))
      (node (ref "C7") (pin "1") (pinfunction "1_1") (pintype "passive"))
      (node (ref "C8") (pin "1") (pinfunction "1_1") (pintype "passive"))
      (node (ref "C9") (pin "2") (pinfunction "2_2") (pintype "passive"))
      (node (ref "J1") (pin "6") (pinfunction "GND_6") (pintype "power_in"))
      (node (ref "J2") (pin "2") (pinfunction "GND_2") (pintype "power_in"))
      (node (ref "J3") (pin "2") (pinfunction "GND_2") (pintype "power_in"))
      (node (ref "J4") (pin "2") (pinfunction "GND_2") (pintype "power_in"))
      (node (ref "J5") (pin "2") (pinfunction "GND_2") (pintype "power_in"))
      (node (ref "J6") (pin "2") (pinfunction "GND_2") (pintype "power_in"))
      (node (ref "R1") (pin "2") (pinfunction "2_2") (pintype "passive"))
      (node (ref "R10") (pin "1") (pinfunction "1_1") (pintype "passive"))
      (node (ref "R12") (pin "1") (pinfunction "1_1") (pintype "passive"))
      (node (ref "R14") (pin "1") (pinfunction "1_1") (pintype "passive"))
      (node (ref "R2") (pin "2") (pinfunction "2_2") (pintype "passive"))
      (node (ref "R3") (pin "2") (pinfunction "2_2") (pintype "passive"))
      (node (ref "R8") (pin "1") (pinfunction "1_1") (pintype "passive"))
      (node (ref "U1") (pin "2") (pinfunction "GND_2") (pintype "input"))
      (node (ref "U1") (pin "4") (pinfunction "GND_4") (pintype "input"))
      (node (ref "U10") (pin "2") (pinfunction "GND_2") (pintype "power_in"))
      (node (ref "U11") (pin "2") (pinfunction "GND_2") (pintype "power_in"))
      (node (ref "U12") (pin "2") (pinfunction "GND_2") (pintype "power_in"))
      (node (ref "U13") (pin "2") (pinfunction "GND_2") (pintype "power_in"))
      (node (ref "U2") (pin "21") (pinfunction "GND_21") (pintype "power_in"))
      (node (ref "U2") (pin "3") (pinfunction "GND_3") (pintype "power_in"))
      (node (ref "U2") (pin "5") (pinfunction "GND_5") (pintype "power_in"))
      (node (ref "U3") (pin "10") (pinfunction "GND_10") (pintype "power_in"))
      (node (ref "U4") (pin "12") (pinfunction "AGND_12") (pintype "power_in"))
      (node (ref "U4") (pin "7") (pinfunction "GND_7") (pintype "power_in"))
      (node (ref "U5") (pin "2") (pinfunction "GND_2") (pintype "power_in"))
      (node (ref "U6") (pin "3") (pinfunction "GND_3") (pintype "power_in"))
      (node (ref "U7") (pin "3") (pinfunction "GND_3") (pintype "power_in"))
      (node (ref "U8") (pin "3") (pinfunction "GND_3") (pintype "power_in"))
      (node (ref "U9") (pin "3") (pinfunction "GND_3") (pintype "power_in"))
      (node (ref "X1") (pin "2") (pinfunction "GND_2") (pintype "power_in"))
      (node (ref "X1") (pin "4") (pinfunction "GND_4") (pintype "power_in"))
      (node (ref "X2") (pin "2") (pinfunction "GND_2") (pintype "power_in"))
      (node (ref "X2") (pin "4") (pinfunction "GND_4") (pintype "power_in"))
    )
    (net (code "20") (name "HEARTBEAT_LED") (class "Default")
      (node (ref "D1") (pin "2") (pinfunction "A_2") (pintype "passive"))
      (node (ref "U2") (pin "10") (pinfunction "6(PWM)_10") (pintype "bidirectional"))
    )
    (net (code "21") (name "Net-(C16-Pad1)") (class "Default")
      (node (ref "C16") (pin "1") (pinfunction "1_1") (pintype "passive"))
      (node (ref "R5") (pin "1") (pinfunction "1_1") (pintype "passive"))
      (node (ref "R6") (pin "1") (pinfunction "1_1") (pintype "passive"))
    )
    (net (code "22") (name "Net-(CAN-P$1)") (class "Default")
      (node (ref "CAN") (pin "1") (pinfunction "P$1_1") (pintype "passive"))
      (node (ref "R5") (pin "2") (pinfunction "2_2") (pintype "passive"))
    )
    (net (code "23") (name "Net-(D1-C)") (class "Default")
      (node (ref "D1") (pin "1") (pinfunction "C_1") (pintype "passive"))
      (node (ref "R1") (pin "1") (pinfunction "1_1") (pintype "passive"))
    )
    (net (code "24") (name "Net-(D2-C)") (class "Default")
      (node (ref "D2") (pin "1") (pinfunction "C_1") (pintype "passive"))
      (node (ref "R2") (pin "1") (pinfunction "1_1") (pintype "passive"))
    )
    (net (code "25") (name "Net-(D3-C)") (class "Default")
      (node (ref "D3") (pin "1") (pinfunction "C_1") (pintype "passive"))
      (node (ref "R3") (pin "1") (pinfunction "1_1") (pintype "passive"))
    )
    (net (code "26") (name "Net-(S1PD-P$1)") (class "Default")
      (node (ref "R14") (pin "2") (pinfunction "2_2") (pintype "passive"))
      (node (ref "S1PD") (pin "1") (pinfunction "P$1_1") (pintype "passive"))
    )
    (net (code "27") (name "Net-(S1PU-P$2)") (class "Default")
      (node (ref "R7") (pin "1") (pinfunction "1_1") (pintype "passive"))
      (node (ref "S1PU") (pin "2") (pinfunction "P$2_2") (pintype "passive"))
    )
    (net (code "28") (name "Net-(S2PD-P$1)") (class "Default")
      (node (ref "R8") (pin "2") (pinfunction "2_2") (pintype "passive"))
      (node (ref "S2PD") (pin "1") (pinfunction "P$1_1") (pintype "passive"))
    )
    (net (code "29") (name "Net-(S2PU-P$2)") (class "Default")
      (node (ref "R9") (pin "1") (pinfunction "1_1") (pintype "passive"))
      (node (ref "S2PU") (pin "2") (pinfunction "P$2_2") (pintype "passive"))
    )
    (net (code "30") (name "Net-(S3PD-P$1)") (class "Default")
      (node (ref "R10") (pin "2") (pinfunction "2_2") (pintype "passive"))
      (node (ref "S3PD") (pin "1") (pinfunction "P$1_1") (pintype "passive"))
    )
    (net (code "31") (name "Net-(S3PU-P$2)") (class "Default")
      (node (ref "R11") (pin "1") (pinfunction "1_1") (pintype "passive"))
      (node (ref "S3PU") (pin "2") (pinfunction "P$2_2") (pintype "passive"))
    )
    (net (code "32") (name "Net-(S4PD-P$1)") (class "Default")
      (node (ref "R12") (pin "2") (pinfunction "2_2") (pintype "passive"))
      (node (ref "S4PD") (pin "1") (pinfunction "P$1_1") (pintype "passive"))
    )
    (net (code "33") (name "Net-(S4PU-P$2)") (class "Default")
      (node (ref "R13") (pin "1") (pinfunction "1_1") (pintype "passive"))
      (node (ref "S4PU") (pin "2") (pinfunction "P$2_2") (pintype "passive"))
    )
    (net (code "34") (name "Net-(U2-(XTAL1)14)") (class "Default")
      (node (ref "C4") (pin "1") (pinfunction "1_1") (pintype "passive"))
      (node (ref "U2") (pin "7") (pinfunction "(XTAL1)14_7") (pintype "bidirectional"))
      (node (ref "X1") (pin "1") (pinfunction "1_1") (pintype "passive"))
    )
    (net (code "35") (name "Net-(U2-(XTAL2)15)") (class "Default")
      (node (ref "C1") (pin "1") (pinfunction "1_1") (pintype "passive"))
      (node (ref "U2") (pin "8") (pinfunction "(XTAL2)15_8") (pintype "bidirectional"))
      (node (ref "X1") (pin "3") (pinfunction "3_3") (pintype "passive"))
    )
    (net (code "36") (name "Net-(U2-14(A0))") (class "Default")
      (node (ref "U2") (pin "23") (pinfunction "14(A0)_23") (pintype "bidirectional"))
      (node (ref "U3") (pin "18") (pinfunction "~{CS}_18") (pintype "input"))
    )
    (net (code "37") (name "Net-(U2-15(A1))") (class "Default")
      (node (ref "U2") (pin "24") (pinfunction "15(A1)_24") (pintype "bidirectional"))
      (node (ref "U4") (pin "8") (pinfunction "~{CS}/SHDN_8") (pintype "input"))
    )
    (net (code "38") (name "Net-(U2-AREF)") (class "Default")
      (node (ref "C7") (pin "2") (pinfunction "2_2") (pintype "passive"))
      (node (ref "U2") (pin "20") (pinfunction "AREF_20") (pintype "input"))
    )
    (net (code "39") (name "Net-(U3-OSC1)") (class "Default")
      (node (ref "C5") (pin "1") (pinfunction "1_1") (pintype "passive"))
      (node (ref "U3") (pin "9") (pinfunction "OSC1_9") (pintype "bidirectional"))
      (node (ref "X2") (pin "1") (pinfunction "1_1") (pintype "passive"))
    )
    (net (code "40") (name "Net-(U3-OSC2)") (class "Default")
      (node (ref "C9") (pin "1") (pinfunction "1_1") (pintype "passive"))
      (node (ref "U3") (pin "8") (pinfunction "OSC2_8") (pintype "bidirectional"))
      (node (ref "X2") (pin "3") (pinfunction "3_3") (pintype "passive"))
    )
    (net (code "41") (name "Net-(U3-~{RESET})") (class "Default")
      (node (ref "R15") (pin "2") (pinfunction "2_2") (pintype "passive"))
      (node (ref "U3") (pin "19") (pinfunction "~{RESET}_19") (pintype "input"))
    )
    (net (code "42") (name "Net-(U6-CLK)") (class "Default")
      (node (ref "C17") (pin "1") (pinfunction "1_1") (pintype "passive"))
      (node (ref "U6") (pin "8") (pinfunction "CLK_8") (pintype "input"))
    )
    (net (code "43") (name "Net-(U6-COM)") (class "Default")
      (node (ref "C21") (pin "1") (pinfunction "1_1") (pintype "passive"))
      (node (ref "U6") (pin "1") (pinfunction "COM_1") (pintype "bidirectional"))
      (node (ref "U6") (pin "6") (pinfunction "OS_6") (pintype "bidirectional"))
    )
    (net (code "44") (name "Net-(U7-CLK)") (class "Default")
      (node (ref "C18") (pin "1") (pinfunction "1_1") (pintype "passive"))
      (node (ref "U7") (pin "8") (pinfunction "CLK_8") (pintype "input"))
    )
    (net (code "45") (name "Net-(U7-COM)") (class "Default")
      (node (ref "C22") (pin "1") (pinfunction "1_1") (pintype "passive"))
      (node (ref "U7") (pin "1") (pinfunction "COM_1") (pintype "bidirectional"))
      (node (ref "U7") (pin "6") (pinfunction "OS_6") (pintype "bidirectional"))
    )
    (net (code "46") (name "Net-(U8-CLK)") (class "Default")
      (node (ref "C19") (pin "1") (pinfunction "1_1") (pintype "passive"))
      (node (ref "U8") (pin "8") (pinfunction "CLK_8") (pintype "input"))
    )
    (net (code "47") (name "Net-(U8-COM)") (class "Default")
      (node (ref "C23") (pin "1") (pinfunction "1_1") (pintype "passive"))
      (node (ref "U8") (pin "1") (pinfunction "COM_1") (pintype "bidirectional"))
      (node (ref "U8") (pin "6") (pinfunction "OS_6") (pintype "bidirectional"))
    )
    (net (code "48") (name "Net-(U9-CLK)") (class "Default")
      (node (ref "C20") (pin "1") (pinfunction "1_1") (pintype "passive"))
      (node (ref "U9") (pin "8") (pinfunction "CLK_8") (pintype "input"))
    )
    (net (code "49") (name "Net-(U9-COM)") (class "Default")
      (node (ref "C24") (pin "1") (pinfunction "1_1") (pintype "passive"))
      (node (ref "U9") (pin "1") (pinfunction "COM_1") (pintype "bidirectional"))
      (node (ref "U9") (pin "6") (pinfunction "OS_6") (pintype "bidirectional"))
    )
    (net (code "50") (name "RESET") (class "Default")
      (node (ref "J1") (pin "5") (pinfunction "RESET_5") (pintype "output"))
      (node (ref "R4") (pin "2") (pinfunction "2_2") (pintype "passive"))
      (node (ref "U2") (pin "29") (pinfunction "22(~{RESET})_29") (pintype "bidirectional"))
    )
    (net (code "51") (name "SIG1_READ") (class "Default")
      (node (ref "U4") (pin "1") (pinfunction "CH0_1") (pintype "input"))
      (node (ref "U6") (pin "5") (pinfunction "OUT_5") (pintype "output"))
    )
    (net (code "52") (name "SIG2_READ") (class "Default")
      (node (ref "U4") (pin "2") (pinfunction "CH1_2") (pintype "input"))
      (node (ref "U7") (pin "5") (pinfunction "OUT_5") (pintype "output"))
    )
    (net (code "53") (name "SIG3_READ") (class "Default")
      (node (ref "U4") (pin "3") (pinfunction "CH2_3") (pintype "input"))
      (node (ref "U8") (pin "5") (pinfunction "OUT_5") (pintype "output"))
    )
    (net (code "54") (name "SIG4_READ") (class "Default")
      (node (ref "U4") (pin "4") (pinfunction "CH3_4") (pintype "input"))
      (node (ref "U9") (pin "5") (pinfunction "OUT_5") (pintype "output"))
    )
    (net (code "55") (name "unconnected-(J2-CH2-Pad4)") (class "Default")
      (node (ref "J2") (pin "4") (pinfunction "CH2_4") (pintype "output"))
    )
    (net (code "56") (name "unconnected-(J3-CH2-Pad4)") (class "Default")
      (node (ref "J3") (pin "4") (pinfunction "CH2_4") (pintype "output"))
    )
    (net (code "57") (name "unconnected-(J4-CH2-Pad4)") (class "Default")
      (node (ref "J4") (pin "4") (pinfunction "CH2_4") (pintype "output"))
    )
    (net (code "58") (name "unconnected-(J5-CH2-Pad4)") (class "Default")
      (node (ref "J5") (pin "4") (pinfunction "CH2_4") (pintype "output"))
    )
    (net (code "59") (name "unconnected-(U2-(PWM)9-Pad13)") (class "Default")
      (node (ref "U2") (pin "13") (pinfunction "(PWM)9_13") (pintype "bidirectional"))
    )
    (net (code "60") (name "unconnected-(U2-(PWM{slash}CS)10-Pad14)") (class "Default")
      (node (ref "U2") (pin "14") (pinfunction "(PWM/CS)10_14") (pintype "bidirectional"))
    )
    (net (code "61") (name "unconnected-(U2-0-Pad30)") (class "Default")
      (node (ref "U2") (pin "30") (pinfunction "0_30") (pintype "bidirectional"))
    )
    (net (code "62") (name "unconnected-(U2-1-Pad31)") (class "Default")
      (node (ref "U2") (pin "31") (pinfunction "1_31") (pintype "bidirectional"))
    )
    (net (code "63") (name "unconnected-(U2-2-Pad32)") (class "Default")
      (node (ref "U2") (pin "32") (pinfunction "2_32") (pintype "bidirectional"))
    )
    (net (code "64") (name "unconnected-(U2-3(PWM)-Pad1)") (class "Default")
      (node (ref "U2") (pin "1") (pinfunction "3(PWM)_1") (pintype "bidirectional"))
    )
    (net (code "65") (name "unconnected-(U2-4-Pad2)") (class "Default")
      (node (ref "U2") (pin "2") (pinfunction "4_2") (pintype "bidirectional"))
    )
    (net (code "66") (name "unconnected-(U2-7-Pad11)") (class "Default")
      (node (ref "U2") (pin "11") (pinfunction "7_11") (pintype "bidirectional"))
    )
    (net (code "67") (name "unconnected-(U2-8-Pad12)") (class "Default")
      (node (ref "U2") (pin "12") (pinfunction "8_12") (pintype "bidirectional"))
    )
    (net (code "68") (name "unconnected-(U2-16(A2)-Pad25)") (class "Default")
      (node (ref "U2") (pin "25") (pinfunction "16(A2)_25") (pintype "bidirectional"))
    )
    (net (code "69") (name "unconnected-(U2-17(A3)-Pad26)") (class "Default")
      (node (ref "U2") (pin "26") (pinfunction "17(A3)_26") (pintype "bidirectional"))
    )
    (net (code "70") (name "unconnected-(U2-18(A4)-Pad27)") (class "Default")
      (node (ref "U2") (pin "27") (pinfunction "18(A4)_27") (pintype "bidirectional"))
    )
    (net (code "71") (name "unconnected-(U2-19(A5)-Pad28)") (class "Default")
      (node (ref "U2") (pin "28") (pinfunction "19(A5)_28") (pintype "bidirectional"))
    )
    (net (code "72") (name "unconnected-(U2-A6-Pad19)") (class "Default")
      (node (ref "U2") (pin "19") (pinfunction "A6_19") (pintype "bidirectional"))
    )
    (net (code "73") (name "unconnected-(U2-A7-Pad22)") (class "Default")
      (node (ref "U2") (pin "22") (pinfunction "A7_22") (pintype "bidirectional"))
    )
    (net (code "74") (name "unconnected-(U3-CLKOUT-Pad3)") (class "Default")
      (node (ref "U3") (pin "3") (pinfunction "CLKOUT_3") (pintype "output"))
    )
    (net (code "75") (name "unconnected-(U3-~{INT}-Pad13)") (class "Default")
      (node (ref "U3") (pin "13") (pinfunction "~{INT}_13") (pintype "output"))
    )
    (net (code "76") (name "unconnected-(U3-~{RX0BF}-Pad12)") (class "Default")
      (node (ref "U3") (pin "12") (pinfunction "~{RX0BF}_12") (pintype "output"))
    )
    (net (code "77") (name "unconnected-(U3-~{RX1BF}-Pad11)") (class "Default")
      (node (ref "U3") (pin "11") (pinfunction "~{RX1BF}_11") (pintype "output"))
    )
    (net (code "78") (name "unconnected-(U3-~{TX0RTS}-Pad4)") (class "Default")
      (node (ref "U3") (pin "4") (pinfunction "~{TX0RTS}_4") (pintype "input"))
    )
    (net (code "79") (name "unconnected-(U3-~{TX1RTS}-Pad5)") (class "Default")
      (node (ref "U3") (pin "5") (pinfunction "~{TX1RTS}_5") (pintype "input"))
    )
    (net (code "80") (name "unconnected-(U3-~{TX2RTS}-Pad7)") (class "Default")
      (node (ref "U3") (pin "7") (pinfunction "~{TX2RTS}_7") (pintype "input"))
    )
    (net (code "81") (name "unconnected-(U5-S-Pad8)") (class "Default")
      (node (ref "U5") (pin "8") (pinfunction "S_8") (pintype "input"))
    )
  )
)
